# PCFX_Mouse_rev_A.net
KiCad netlist of a schematic drawn in EAGLE
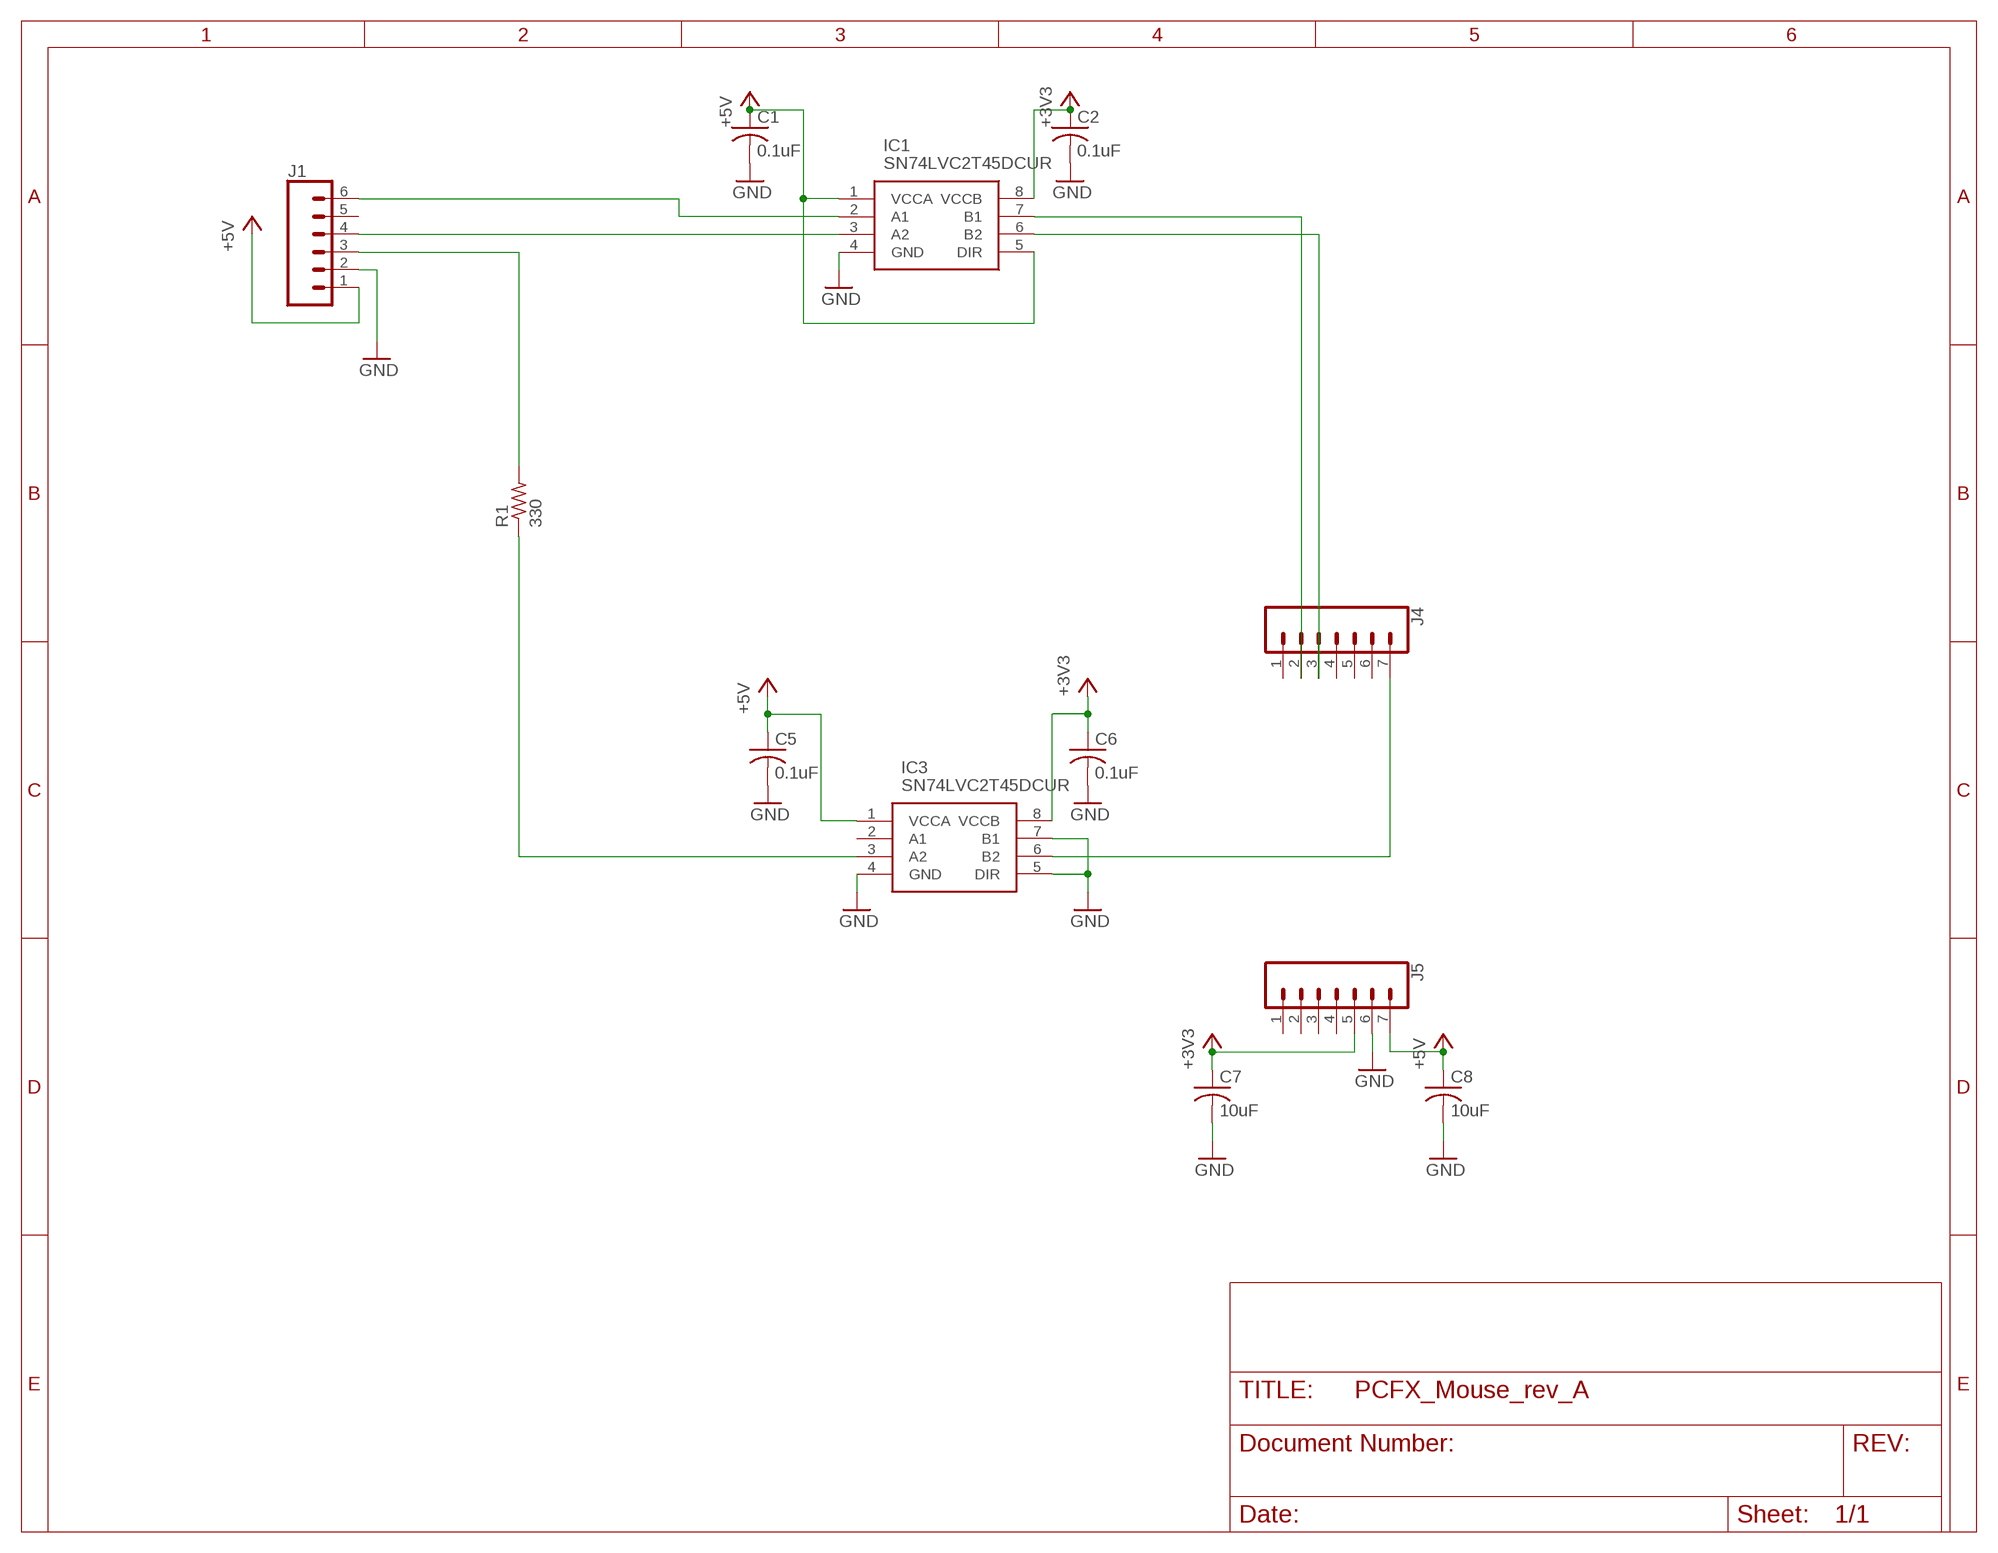
[diagram p0: schematic, sheet 1]

(export (version "E")
  (design (tool "Eeschema 10.0.6"))
  (components
    (comp (ref "C1")
      (value "0.1uF")
      (footprint "eagle-import:C0402")
      (libsource (lib "eagle-import") (part "C-USC0402"))
    )
    (comp (ref "C2")
      (value "0.1uF")
      (footprint "eagle-import:C0402")
      (libsource (lib "eagle-import") (part "C-USC0402"))
    )
    (comp (ref "C5")
      (value "0.1uF")
      (footprint "eagle-import:C0402")
      (libsource (lib "eagle-import") (part "C-USC0402"))
    )
    (comp (ref "C6")
      (value "0.1uF")
      (footprint "eagle-import:C0402")
      (libsource (lib "eagle-import") (part "C-USC0402"))
    )
    (comp (ref "C7")
      (value "10uF")
      (footprint "eagle-import:C0805")
      (libsource (lib "eagle-import") (part "C-USC0805"))
    )
    (comp (ref "C8")
      (value "10uF")
      (footprint "eagle-import:C0805")
      (libsource (lib "eagle-import") (part "C-USC0805"))
    )
    (comp (ref "IC1")
      (value "SN74LVC2T45DCUR")
      (footprint "eagle-import:SOP50P310X90-8N")
      (fields (field (name "MOUSER_PART_NUMBER") "595-SN74LVC2T45DCUR"))
      (libsource (lib "eagle-import") (part "SN74LVC2T45DCUR"))
    )
    (comp (ref "IC3")
      (value "SN74LVC2T45DCUR")
      (footprint "eagle-import:SOP50P310X90-8N")
      (fields (field (name "MOUSER_PART_NUMBER") "595-SN74LVC2T45DCUR"))
      (libsource (lib "eagle-import") (part "SN74LVC2T45DCUR"))
    )
    (comp (ref "J1")
      (value "CONN_06NO_SILK_FEMALE_PTH")
      (footprint "eagle-import:1X06_NO_SILK")
      (libsource (lib "eagle-import") (part "CONN_06NO_SILK_FEMALE_PTH"))
    )
    (comp (ref "J4")
      (value "CONN_07LONGPADS")
      (footprint "eagle-import:1X07_LONGPADS")
      (libsource (lib "eagle-import") (part "CONN_07LONGPADS"))
    )
    (comp (ref "J5")
      (value "CONN_07LONGPADS")
      (footprint "eagle-import:1X07_LONGPADS")
      (libsource (lib "eagle-import") (part "CONN_07LONGPADS"))
    )
    (comp (ref "R1")
      (value "330")
      (footprint "eagle-import:R0402")
      (libsource (lib "eagle-import") (part "R-US_R0402"))
    )
  )
  (nets
    (net (code "1") (name "+3V3") (class "Default")
      (node (ref "C2") (pin "1") (pinfunction "1_1") (pintype "passive"))
      (node (ref "C6") (pin "1") (pinfunction "1_1") (pintype "passive"))
      (node (ref "C7") (pin "1") (pinfunction "1_1") (pintype "passive"))
      (node (ref "IC1") (pin "8") (pinfunction "VCCB_8") (pintype "bidirectional"))
      (node (ref "IC3") (pin "8") (pinfunction "VCCB_8") (pintype "bidirectional"))
      (node (ref "J5") (pin "5") (pinfunction "5_5") (pintype "passive"))
    )
    (net (code "2") (name "+5V") (class "Default")
      (node (ref "C1") (pin "1") (pinfunction "1_1") (pintype "passive"))
      (node (ref "C5") (pin "1") (pinfunction "1_1") (pintype "passive"))
      (node (ref "C8") (pin "1") (pinfunction "1_1") (pintype "passive"))
      (node (ref "IC1") (pin "1") (pinfunction "VCCA_1") (pintype "bidirectional"))
      (node (ref "IC1") (pin "5") (pinfunction "DIR_5") (pintype "bidirectional"))
      (node (ref "IC3") (pin "1") (pinfunction "VCCA_1") (pintype "bidirectional"))
      (node (ref "J1") (pin "1") (pinfunction "1_1") (pintype "passive"))
      (node (ref "J5") (pin "7") (pinfunction "7_7") (pintype "passive"))
    )
    (net (code "3") (name "GND") (class "Default")
      (node (ref "C1") (pin "2") (pinfunction "2_2") (pintype "passive"))
      (node (ref "C2") (pin "2") (pinfunction "2_2") (pintype "passive"))
      (node (ref "C5") (pin "2") (pinfunction "2_2") (pintype "passive"))
      (node (ref "C6") (pin "2") (pinfunction "2_2") (pintype "passive"))
      (node (ref "C7") (pin "2") (pinfunction "2_2") (pintype "passive"))
      (node (ref "C8") (pin "2") (pinfunction "2_2") (pintype "passive"))
      (node (ref "IC1") (pin "4") (pinfunction "GND_4") (pintype "bidirectional"))
      (node (ref "IC3") (pin "4") (pinfunction "GND_4") (pintype "bidirectional"))
      (node (ref "IC3") (pin "5") (pinfunction "DIR_5") (pintype "bidirectional"))
      (node (ref "IC3") (pin "7") (pinfunction "B1_7") (pintype "bidirectional"))
      (node (ref "J1") (pin "2") (pinfunction "2_2") (pintype "passive"))
      (node (ref "J5") (pin "6") (pinfunction "6_6") (pintype "passive"))
    )
    (net (code "4") (name "Net-(IC1-A1)") (class "Default")
      (node (ref "IC1") (pin "2") (pinfunction "A1_2") (pintype "bidirectional"))
      (node (ref "J1") (pin "6") (pinfunction "6_6") (pintype "passive"))
    )
    (net (code "5") (name "Net-(IC1-A2)") (class "Default")
      (node (ref "IC1") (pin "3") (pinfunction "A2_3") (pintype "bidirectional"))
      (node (ref "J1") (pin "4") (pinfunction "4_4") (pintype "passive"))
    )
    (net (code "6") (name "Net-(IC1-B1)") (class "Default")
      (node (ref "IC1") (pin "7") (pinfunction "B1_7") (pintype "bidirectional"))
      (node (ref "J4") (pin "2") (pinfunction "2_2") (pintype "passive"))
    )
    (net (code "7") (name "Net-(IC1-B2)") (class "Default")
      (node (ref "IC1") (pin "6") (pinfunction "B2_6") (pintype "bidirectional"))
      (node (ref "J4") (pin "3") (pinfunction "3_3") (pintype "passive"))
    )
    (net (code "8") (name "Net-(IC3-A2)") (class "Default")
      (node (ref "IC3") (pin "3") (pinfunction "A2_3") (pintype "bidirectional"))
      (node (ref "R1") (pin "1") (pinfunction "1_1") (pintype "passive"))
    )
    (net (code "9") (name "Net-(IC3-B2)") (class "Default")
      (node (ref "IC3") (pin "6") (pinfunction "B2_6") (pintype "bidirectional"))
      (node (ref "J4") (pin "7") (pinfunction "7_7") (pintype "passive"))
    )
    (net (code "10") (name "Net-(J1-Pad3)") (class "Default")
      (node (ref "J1") (pin "3") (pinfunction "3_3") (pintype "passive"))
      (node (ref "R1") (pin "2") (pinfunction "2_2") (pintype "passive"))
    )
    (net (code "11") (name "unconnected-(IC3-A1-Pad2)") (class "Default")
      (node (ref "IC3") (pin "2") (pinfunction "A1_2") (pintype "bidirectional"))
    )
    (net (code "12") (name "unconnected-(J1-Pad5)") (class "Default")
      (node (ref "J1") (pin "5") (pinfunction "5_5") (pintype "passive"))
    )
    (net (code "13") (name "unconnected-(J4-Pad1)") (class "Default")
      (node (ref "J4") (pin "1") (pinfunction "1_1") (pintype "passive"))
    )
    (net (code "14") (name "unconnected-(J4-Pad4)") (class "Default")
      (node (ref "J4") (pin "4") (pinfunction "4_4") (pintype "passive"))
    )
    (net (code "15") (name "unconnected-(J4-Pad5)") (class "Default")
      (node (ref "J4") (pin "5") (pinfunction "5_5") (pintype "passive"))
    )
    (net (code "16") (name "unconnected-(J4-Pad6)") (class "Default")
      (node (ref "J4") (pin "6") (pinfunction "6_6") (pintype "passive"))
    )
    (net (code "17") (name "unconnected-(J5-Pad1)") (class "Default")
      (node (ref "J5") (pin "1") (pinfunction "1_1") (pintype "passive"))
    )
    (net (code "18") (name "unconnected-(J5-Pad2)") (class "Default")
      (node (ref "J5") (pin "2") (pinfunction "2_2") (pintype "passive"))
    )
    (net (code "19") (name "unconnected-(J5-Pad3)") (class "Default")
      (node (ref "J5") (pin "3") (pinfunction "3_3") (pintype "passive"))
    )
    (net (code "20") (name "unconnected-(J5-Pad4)") (class "Default")
      (node (ref "J5") (pin "4") (pinfunction "4_4") (pintype "passive"))
    )
  )
)
